# mgmt.net
KiCad netlist of a schematic drawn in Altium Designer
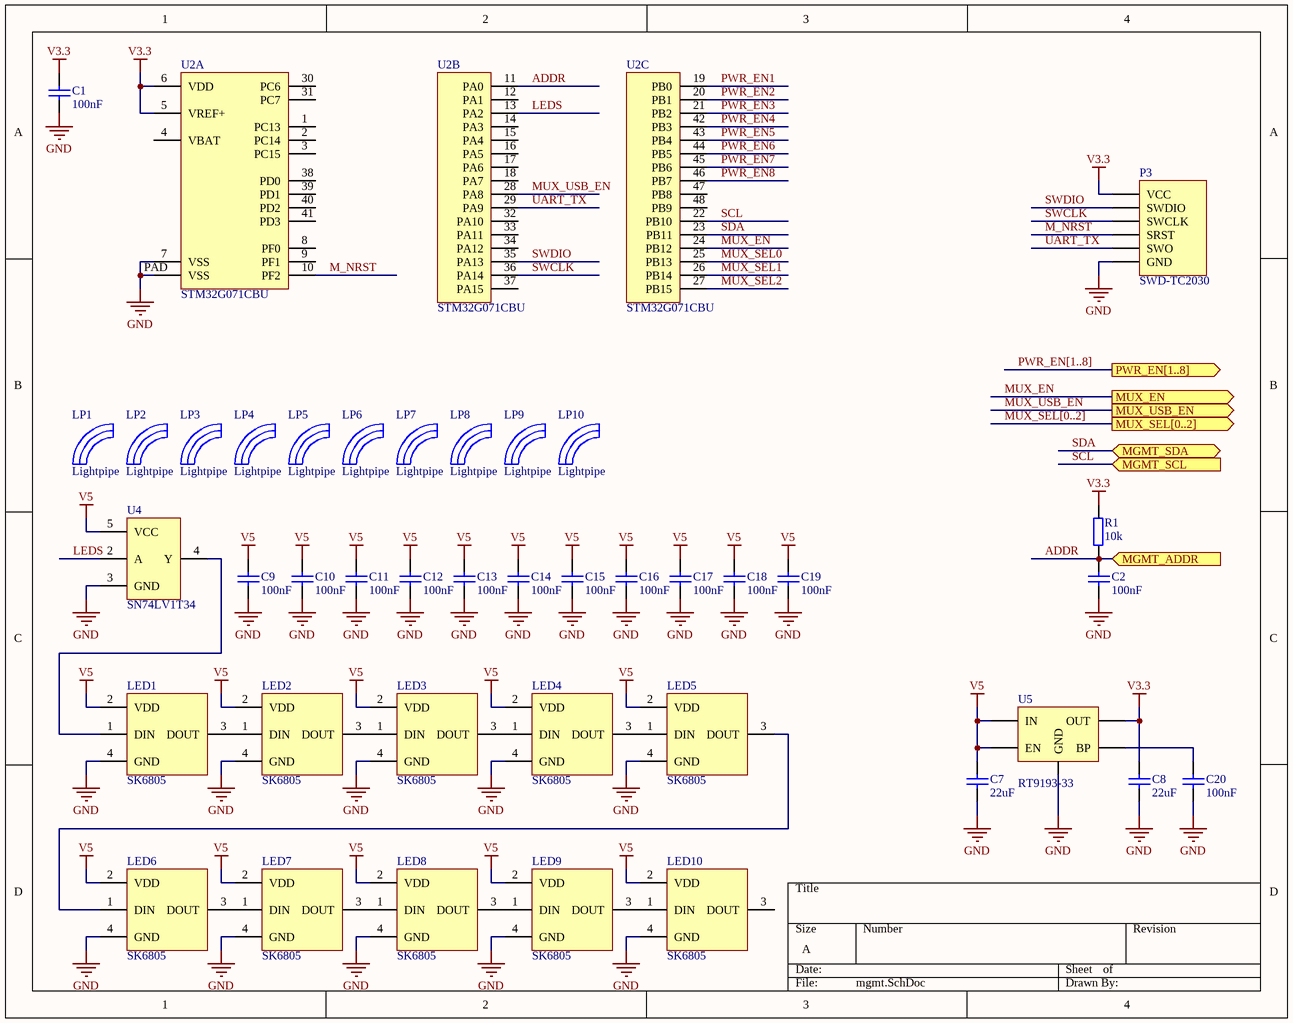
[diagram p0: mgmt.SchDoc]

(export (version "E")
  (design (tool "Eeschema 10.0.6"))
  (components
    (comp (ref "C1") (value "100nF") (footprint "0402") (libsource (lib "misc") (part "Capacitor")))
    (comp (ref "C2") (value "100nF") (footprint "0402") (libsource (lib "misc") (part "Capacitor")))
    (comp (ref "C7") (value "22uF") (footprint "0805") (libsource (lib "misc") (part "Capacitor")))
    (comp (ref "C8") (value "22uF") (footprint "0805") (libsource (lib "misc") (part "Capacitor")))
    (comp (ref "C9") (value "100nF") (footprint "0402") (libsource (lib "misc") (part "Capacitor")))
    (comp (ref "C10") (value "100nF") (footprint "0402") (libsource (lib "misc") (part "Capacitor")))
    (comp (ref "C11") (value "100nF") (footprint "0402") (libsource (lib "misc") (part "Capacitor")))
    (comp (ref "C12") (value "100nF") (footprint "0402") (libsource (lib "misc") (part "Capacitor")))
    (comp (ref "C13") (value "100nF") (footprint "0402") (libsource (lib "misc") (part "Capacitor")))
    (comp (ref "C14") (value "100nF") (footprint "0402") (libsource (lib "misc") (part "Capacitor")))
    (comp (ref "C15") (value "100nF") (footprint "0402") (libsource (lib "misc") (part "Capacitor")))
    (comp (ref "C16") (value "100nF") (footprint "0402") (libsource (lib "misc") (part "Capacitor")))
    (comp (ref "C17") (value "100nF") (footprint "0402") (libsource (lib "misc") (part "Capacitor")))
    (comp (ref "C18") (value "100nF") (footprint "0402") (libsource (lib "misc") (part "Capacitor")))
    (comp (ref "C19") (value "100nF") (footprint "0402") (libsource (lib "misc") (part "Capacitor")))
    (comp (ref "C20") (value "100nF") (footprint "0402") (libsource (lib "misc") (part "Capacitor")))
    (comp (ref "LED1") (value "SK6805") (footprint "EC15") (libsource (lib "misc") (part "SK6805")))
    (comp (ref "LED2") (value "SK6805") (footprint "EC15") (libsource (lib "misc") (part "SK6805")))
    (comp (ref "LED3") (value "SK6805") (footprint "EC15") (libsource (lib "misc") (part "SK6805")))
    (comp (ref "LED4") (value "SK6805") (footprint "EC15") (libsource (lib "misc") (part "SK6805")))
    (comp (ref "LED5") (value "SK6805") (footprint "EC15") (libsource (lib "misc") (part "SK6805")))
    (comp (ref "LED6") (value "SK6805") (footprint "EC15") (libsource (lib "misc") (part "SK6805")))
    (comp (ref "LED7") (value "SK6805") (footprint "EC15") (libsource (lib "misc") (part "SK6805")))
    (comp (ref "LED8") (value "SK6805") (footprint "EC15") (libsource (lib "misc") (part "SK6805")))
    (comp (ref "LED9") (value "SK6805") (footprint "EC15") (libsource (lib "misc") (part "SK6805")))
    (comp (ref "LED10") (value "SK6805") (footprint "EC15") (libsource (lib "misc") (part "SK6805")))
    (comp (ref "LP1")
      (value "Lightpipe")
      (footprint "SLP3-150-100-F")
      (libsource (lib "misc") (part "Lightpipe"))
    )
    (comp (ref "LP2")
      (value "Lightpipe")
      (footprint "SLP3-150-100-F")
      (libsource (lib "misc") (part "Lightpipe"))
    )
    (comp (ref "LP3")
      (value "Lightpipe")
      (footprint "SLP3-150-100-F")
      (libsource (lib "misc") (part "Lightpipe"))
    )
    (comp (ref "LP4")
      (value "Lightpipe")
      (footprint "SLP3-150-100-F")
      (libsource (lib "misc") (part "Lightpipe"))
    )
    (comp (ref "LP5")
      (value "Lightpipe")
      (footprint "SLP3-150-100-F")
      (libsource (lib "misc") (part "Lightpipe"))
    )
    (comp (ref "LP6")
      (value "Lightpipe")
      (footprint "SLP3-150-100-F")
      (libsource (lib "misc") (part "Lightpipe"))
    )
    (comp (ref "LP7")
      (value "Lightpipe")
      (footprint "SLP3-150-100-F")
      (libsource (lib "misc") (part "Lightpipe"))
    )
    (comp (ref "LP8")
      (value "Lightpipe")
      (footprint "SLP3-150-100-F")
      (libsource (lib "misc") (part "Lightpipe"))
    )
    (comp (ref "LP9")
      (value "Lightpipe")
      (footprint "SLP3-150-100-F")
      (libsource (lib "misc") (part "Lightpipe"))
    )
    (comp (ref "LP10")
      (value "Lightpipe")
      (footprint "SLP3-150-100-F")
      (libsource (lib "misc") (part "Lightpipe"))
    )
    (comp (ref "P3")
      (value "SWD-TC2030")
      (footprint "TC2030-NL")
      (libsource (lib "misc") (part "SWD-TC2030"))
    )
    (comp (ref "R1") (value "10k") (footprint "0402") (libsource (lib "misc") (part "Resistor")))
    (comp (ref "U2")
      (value "STM32G071CBU")
      (footprint "QFN50P690X710X60_HS-49N")
      (libsource (lib "misc") (part "STM32G0B1CxU"))
    )
    (comp (ref "U4")
      (value "SN74LV1T34")
      (footprint "SOT23-5")
      (description "Single Power Supply Single Buffer GATE CMOS Logic Level Shifter")
      (libsource (lib "misc") (part "SN74LV1T34"))
    )
    (comp (ref "U5") (value "RT9193-33") (footprint "SOT23-5") (libsource (lib "misc") (part "VREG_EN_BP")))
  )
  (nets
    (net (code "1") (name "/ADDR") (class "Default")
      (node (ref "C2") (pin "2") (pinfunction "2_2") (pintype "passive"))
      (node (ref "R1") (pin "1") (pinfunction "1_1") (pintype "passive"))
      (node (ref "U2") (pin "11") (pinfunction "PA0_11") (pintype "passive"))
    )
    (net (code "2") (name "/LEDS") (class "Default")
      (node (ref "U2") (pin "13") (pinfunction "PA2_13") (pintype "passive"))
      (node (ref "U4") (pin "2") (pinfunction "A_2") (pintype "passive"))
    )
    (net (code "3") (name "/MUX_EN") (class "Default")
      (node (ref "U2") (pin "24") (pinfunction "PB12_24") (pintype "passive"))
    )
    (net (code "4") (name "/MUX_SEL0") (class "Default")
      (node (ref "U2") (pin "25") (pinfunction "PB13_25") (pintype "passive"))
    )
    (net (code "5") (name "/MUX_SEL1") (class "Default")
      (node (ref "U2") (pin "26") (pinfunction "PB14_26") (pintype "passive"))
    )
    (net (code "6") (name "/MUX_SEL2") (class "Default")
      (node (ref "U2") (pin "27") (pinfunction "PB15_27") (pintype "passive"))
    )
    (net (code "8") (name "/MUX_USB_EN") (class "Default")
      (node (ref "U2") (pin "28") (pinfunction "PA8_28") (pintype "passive"))
    )
    (net (code "9") (name "/M_NRST") (class "Default")
      (node (ref "P3") (pin "SRST") (pinfunction "SRST_SRST") (pintype "passive"))
      (node (ref "U2") (pin "10") (pinfunction "PF2_10") (pintype "passive"))
    )
    (net (code "10") (name "/PWR_EN1") (class "Default")
      (node (ref "U2") (pin "19") (pinfunction "PB0_19") (pintype "passive"))
    )
    (net (code "11") (name "/PWR_EN2") (class "Default")
      (node (ref "U2") (pin "20") (pinfunction "PB1_20") (pintype "passive"))
    )
    (net (code "12") (name "/PWR_EN3") (class "Default")
      (node (ref "U2") (pin "21") (pinfunction "PB2_21") (pintype "passive"))
    )
    (net (code "13") (name "/PWR_EN4") (class "Default")
      (node (ref "U2") (pin "42") (pinfunction "PB3_42") (pintype "passive"))
    )
    (net (code "14") (name "/PWR_EN5") (class "Default")
      (node (ref "U2") (pin "43") (pinfunction "PB4_43") (pintype "passive"))
    )
    (net (code "15") (name "/PWR_EN6") (class "Default")
      (node (ref "U2") (pin "44") (pinfunction "PB5_44") (pintype "passive"))
    )
    (net (code "16") (name "/PWR_EN7") (class "Default")
      (node (ref "U2") (pin "45") (pinfunction "PB6_45") (pintype "passive"))
    )
    (net (code "17") (name "/PWR_EN8") (class "Default")
      (node (ref "U2") (pin "46") (pinfunction "PB7_46") (pintype "passive"))
    )
    (net (code "19") (name "/SCL") (class "Default")
      (node (ref "U2") (pin "22") (pinfunction "PB10_22") (pintype "passive"))
    )
    (net (code "20") (name "/SDA") (class "Default")
      (node (ref "U2") (pin "23") (pinfunction "PB11_23") (pintype "passive"))
    )
    (net (code "21") (name "/SWCLK") (class "Default")
      (node (ref "P3") (pin "SWCLK") (pinfunction "SWCLK_SWCLK") (pintype "passive"))
      (node (ref "U2") (pin "36") (pinfunction "PA14_36") (pintype "passive"))
    )
    (net (code "22") (name "/SWDIO") (class "Default")
      (node (ref "P3") (pin "SWDIO") (pinfunction "SWDIO_SWDIO") (pintype "passive"))
      (node (ref "U2") (pin "35") (pinfunction "PA13_35") (pintype "passive"))
    )
    (net (code "23") (name "/UART_TX") (class "Default")
      (node (ref "P3") (pin "SWO") (pinfunction "SWO_SWO") (pintype "passive"))
      (node (ref "U2") (pin "29") (pinfunction "PA9_29") (pintype "passive"))
    )
    (net (code "24") (name "GND") (class "Default")
      (node (ref "C1") (pin "1") (pinfunction "1_1") (pintype "passive"))
      (node (ref "C10") (pin "1") (pinfunction "1_1") (pintype "passive"))
      (node (ref "C11") (pin "1") (pinfunction "1_1") (pintype "passive"))
      (node (ref "C12") (pin "1") (pinfunction "1_1") (pintype "passive"))
      (node (ref "C13") (pin "1") (pinfunction "1_1") (pintype "passive"))
      (node (ref "C14") (pin "1") (pinfunction "1_1") (pintype "passive"))
      (node (ref "C15") (pin "1") (pinfunction "1_1") (pintype "passive"))
      (node (ref "C16") (pin "1") (pinfunction "1_1") (pintype "passive"))
      (node (ref "C17") (pin "1") (pinfunction "1_1") (pintype "passive"))
      (node (ref "C18") (pin "1") (pinfunction "1_1") (pintype "passive"))
      (node (ref "C19") (pin "1") (pinfunction "1_1") (pintype "passive"))
      (node (ref "C2") (pin "1") (pinfunction "1_1") (pintype "passive"))
      (node (ref "C20") (pin "1") (pinfunction "1_1") (pintype "passive"))
      (node (ref "C7") (pin "1") (pinfunction "1_1") (pintype "passive"))
      (node (ref "C8") (pin "1") (pinfunction "1_1") (pintype "passive"))
      (node (ref "C9") (pin "1") (pinfunction "1_1") (pintype "passive"))
      (node (ref "LED1") (pin "4") (pinfunction "GND_4") (pintype "passive"))
      (node (ref "LED10") (pin "4") (pinfunction "GND_4") (pintype "passive"))
      (node (ref "LED2") (pin "4") (pinfunction "GND_4") (pintype "passive"))
      (node (ref "LED3") (pin "4") (pinfunction "GND_4") (pintype "passive"))
      (node (ref "LED4") (pin "4") (pinfunction "GND_4") (pintype "passive"))
      (node (ref "LED5") (pin "4") (pinfunction "GND_4") (pintype "passive"))
      (node (ref "LED6") (pin "4") (pinfunction "GND_4") (pintype "passive"))
      (node (ref "LED7") (pin "4") (pinfunction "GND_4") (pintype "passive"))
      (node (ref "LED8") (pin "4") (pinfunction "GND_4") (pintype "passive"))
      (node (ref "LED9") (pin "4") (pinfunction "GND_4") (pintype "passive"))
      (node (ref "P3") (pin "GND") (pinfunction "GND_GND") (pintype "passive"))
      (node (ref "U2") (pin "7") (pinfunction "VSS_7") (pintype "passive"))
      (node (ref "U2") (pin "PAD") (pinfunction "VSS_PAD") (pintype "passive"))
      (node (ref "U4") (pin "3") (pinfunction "GND_3") (pintype "passive"))
      (node (ref "U5") (pin "GND") (pinfunction "GND_GND") (pintype "passive"))
    )
    (net (code "25") (name "Net-(C20-Pad2)") (class "Default")
      (node (ref "C20") (pin "2") (pinfunction "2_2") (pintype "passive"))
      (node (ref "U5") (pin "BP") (pinfunction "BP_BP") (pintype "passive"))
    )
    (net (code "26") (name "Net-(LED1-DIN)") (class "Default")
      (node (ref "LED1") (pin "1") (pinfunction "DIN_1") (pintype "passive"))
      (node (ref "U4") (pin "4") (pinfunction "Y_4") (pintype "passive"))
    )
    (net (code "27") (name "Net-(LED1-DOUT)") (class "Default")
      (node (ref "LED1") (pin "3") (pinfunction "DOUT_3") (pintype "passive"))
      (node (ref "LED2") (pin "1") (pinfunction "DIN_1") (pintype "passive"))
    )
    (net (code "28") (name "Net-(LED2-DOUT)") (class "Default")
      (node (ref "LED2") (pin "3") (pinfunction "DOUT_3") (pintype "passive"))
      (node (ref "LED3") (pin "1") (pinfunction "DIN_1") (pintype "passive"))
    )
    (net (code "29") (name "Net-(LED3-DOUT)") (class "Default")
      (node (ref "LED3") (pin "3") (pinfunction "DOUT_3") (pintype "passive"))
      (node (ref "LED4") (pin "1") (pinfunction "DIN_1") (pintype "passive"))
    )
    (net (code "30") (name "Net-(LED4-DOUT)") (class "Default")
      (node (ref "LED4") (pin "3") (pinfunction "DOUT_3") (pintype "passive"))
      (node (ref "LED5") (pin "1") (pinfunction "DIN_1") (pintype "passive"))
    )
    (net (code "31") (name "Net-(LED5-DOUT)") (class "Default")
      (node (ref "LED5") (pin "3") (pinfunction "DOUT_3") (pintype "passive"))
      (node (ref "LED6") (pin "1") (pinfunction "DIN_1") (pintype "passive"))
    )
    (net (code "32") (name "Net-(LED6-DOUT)") (class "Default")
      (node (ref "LED6") (pin "3") (pinfunction "DOUT_3") (pintype "passive"))
      (node (ref "LED7") (pin "1") (pinfunction "DIN_1") (pintype "passive"))
    )
    (net (code "33") (name "Net-(LED7-DOUT)") (class "Default")
      (node (ref "LED7") (pin "3") (pinfunction "DOUT_3") (pintype "passive"))
      (node (ref "LED8") (pin "1") (pinfunction "DIN_1") (pintype "passive"))
    )
    (net (code "34") (name "Net-(LED8-DOUT)") (class "Default")
      (node (ref "LED8") (pin "3") (pinfunction "DOUT_3") (pintype "passive"))
      (node (ref "LED9") (pin "1") (pinfunction "DIN_1") (pintype "passive"))
    )
    (net (code "35") (name "Net-(LED10-DIN)") (class "Default")
      (node (ref "LED10") (pin "1") (pinfunction "DIN_1") (pintype "passive"))
      (node (ref "LED9") (pin "3") (pinfunction "DOUT_3") (pintype "passive"))
    )
    (net (code "36") (name "V3.3") (class "Default")
      (node (ref "C1") (pin "2") (pinfunction "2_2") (pintype "passive"))
      (node (ref "C8") (pin "2") (pinfunction "2_2") (pintype "passive"))
      (node (ref "P3") (pin "VCC") (pinfunction "VCC_VCC") (pintype "passive"))
      (node (ref "R1") (pin "2") (pinfunction "2_2") (pintype "passive"))
      (node (ref "U2") (pin "5") (pinfunction "VREF+_5") (pintype "passive"))
      (node (ref "U2") (pin "6") (pinfunction "VDD_6") (pintype "passive"))
      (node (ref "U5") (pin "OUT") (pinfunction "OUT_OUT") (pintype "passive"))
    )
    (net (code "37") (name "V5") (class "Default")
      (node (ref "C10") (pin "2") (pinfunction "2_2") (pintype "passive"))
      (node (ref "C11") (pin "2") (pinfunction "2_2") (pintype "passive"))
      (node (ref "C12") (pin "2") (pinfunction "2_2") (pintype "passive"))
      (node (ref "C13") (pin "2") (pinfunction "2_2") (pintype "passive"))
      (node (ref "C14") (pin "2") (pinfunction "2_2") (pintype "passive"))
      (node (ref "C15") (pin "2") (pinfunction "2_2") (pintype "passive"))
      (node (ref "C16") (pin "2") (pinfunction "2_2") (pintype "passive"))
      (node (ref "C17") (pin "2") (pinfunction "2_2") (pintype "passive"))
      (node (ref "C18") (pin "2") (pinfunction "2_2") (pintype "passive"))
      (node (ref "C19") (pin "2") (pinfunction "2_2") (pintype "passive"))
      (node (ref "C7") (pin "2") (pinfunction "2_2") (pintype "passive"))
      (node (ref "C9") (pin "2") (pinfunction "2_2") (pintype "passive"))
      (node (ref "LED1") (pin "2") (pinfunction "VDD_2") (pintype "passive"))
      (node (ref "LED10") (pin "2") (pinfunction "VDD_2") (pintype "passive"))
      (node (ref "LED2") (pin "2") (pinfunction "VDD_2") (pintype "passive"))
      (node (ref "LED3") (pin "2") (pinfunction "VDD_2") (pintype "passive"))
      (node (ref "LED4") (pin "2") (pinfunction "VDD_2") (pintype "passive"))
      (node (ref "LED5") (pin "2") (pinfunction "VDD_2") (pintype "passive"))
      (node (ref "LED6") (pin "2") (pinfunction "VDD_2") (pintype "passive"))
      (node (ref "LED7") (pin "2") (pinfunction "VDD_2") (pintype "passive"))
      (node (ref "LED8") (pin "2") (pinfunction "VDD_2") (pintype "passive"))
      (node (ref "LED9") (pin "2") (pinfunction "VDD_2") (pintype "passive"))
      (node (ref "U4") (pin "5") (pinfunction "VCC_5") (pintype "passive"))
      (node (ref "U5") (pin "EN") (pinfunction "EN_EN") (pintype "passive"))
      (node (ref "U5") (pin "IN") (pinfunction "IN_IN") (pintype "passive"))
    )
    (net (code "38") (name "unconnected-(LED10-DOUT-Pad3)") (class "Default")
      (node (ref "LED10") (pin "3") (pinfunction "DOUT_3") (pintype "passive"))
    )
    (net (code "39") (name "unconnected-(U2A-PC6-Pad30)") (class "Default")
      (node (ref "U2") (pin "30") (pinfunction "PC6_30") (pintype "passive"))
    )
    (net (code "40") (name "unconnected-(U2A-PC7-Pad31)") (class "Default")
      (node (ref "U2") (pin "31") (pinfunction "PC7_31") (pintype "passive"))
    )
    (net (code "41") (name "unconnected-(U2A-PC13-Pad1)") (class "Default")
      (node (ref "U2") (pin "1") (pinfunction "PC13_1") (pintype "passive"))
    )
    (net (code "42") (name "unconnected-(U2A-PC14-Pad2)") (class "Default")
      (node (ref "U2") (pin "2") (pinfunction "PC14_2") (pintype "passive"))
    )
    (net (code "43") (name "unconnected-(U2A-PC15-Pad3)") (class "Default")
      (node (ref "U2") (pin "3") (pinfunction "PC15_3") (pintype "passive"))
    )
    (net (code "44") (name "unconnected-(U2A-PD0-Pad38)") (class "Default")
      (node (ref "U2") (pin "38") (pinfunction "PD0_38") (pintype "passive"))
    )
    (net (code "45") (name "unconnected-(U2A-PD1-Pad39)") (class "Default")
      (node (ref "U2") (pin "39") (pinfunction "PD1_39") (pintype "passive"))
    )
    (net (code "46") (name "unconnected-(U2A-PD2-Pad40)") (class "Default")
      (node (ref "U2") (pin "40") (pinfunction "PD2_40") (pintype "passive"))
    )
    (net (code "47") (name "unconnected-(U2A-PD3-Pad41)") (class "Default")
      (node (ref "U2") (pin "41") (pinfunction "PD3_41") (pintype "passive"))
    )
    (net (code "48") (name "unconnected-(U2A-PF0-Pad8)") (class "Default")
      (node (ref "U2") (pin "8") (pinfunction "PF0_8") (pintype "passive"))
    )
    (net (code "49") (name "unconnected-(U2A-PF1-Pad9)") (class "Default")
      (node (ref "U2") (pin "9") (pinfunction "PF1_9") (pintype "passive"))
    )
    (net (code "50") (name "unconnected-(U2A-VBAT-Pad4)") (class "Default")
      (node (ref "U2") (pin "4") (pinfunction "VBAT_4") (pintype "passive"))
    )
    (net (code "51") (name "unconnected-(U2B-PA1-Pad12)") (class "Default")
      (node (ref "U2") (pin "12") (pinfunction "PA1_12") (pintype "passive"))
    )
    (net (code "52") (name "unconnected-(U2B-PA3-Pad14)") (class "Default")
      (node (ref "U2") (pin "14") (pinfunction "PA3_14") (pintype "passive"))
    )
    (net (code "53") (name "unconnected-(U2B-PA4-Pad15)") (class "Default")
      (node (ref "U2") (pin "15") (pinfunction "PA4_15") (pintype "passive"))
    )
    (net (code "54") (name "unconnected-(U2B-PA5-Pad16)") (class "Default")
      (node (ref "U2") (pin "16") (pinfunction "PA5_16") (pintype "passive"))
    )
    (net (code "55") (name "unconnected-(U2B-PA6-Pad17)") (class "Default")
      (node (ref "U2") (pin "17") (pinfunction "PA6_17") (pintype "passive"))
    )
    (net (code "56") (name "unconnected-(U2B-PA7-Pad18)") (class "Default")
      (node (ref "U2") (pin "18") (pinfunction "PA7_18") (pintype "passive"))
    )
    (net (code "57") (name "unconnected-(U2B-PA10-Pad32)") (class "Default")
      (node (ref "U2") (pin "32") (pinfunction "PA10_32") (pintype "passive"))
    )
    (net (code "58") (name "unconnected-(U2B-PA11-Pad33)") (class "Default")
      (node (ref "U2") (pin "33") (pinfunction "PA11_33") (pintype "passive"))
    )
    (net (code "59") (name "unconnected-(U2B-PA12-Pad34)") (class "Default")
      (node (ref "U2") (pin "34") (pinfunction "PA12_34") (pintype "passive"))
    )
    (net (code "60") (name "unconnected-(U2B-PA15-Pad37)") (class "Default")
      (node (ref "U2") (pin "37") (pinfunction "PA15_37") (pintype "passive"))
    )
    (net (code "61") (name "unconnected-(U2C-PB8-Pad47)") (class "Default")
      (node (ref "U2") (pin "47") (pinfunction "PB8_47") (pintype "passive"))
    )
    (net (code "62") (name "unconnected-(U2C-PB9-Pad48)") (class "Default")
      (node (ref "U2") (pin "48") (pinfunction "PB9_48") (pintype "passive"))
    )
  )
)
